# pwr_supply.net
KiCad netlist of a schematic drawn in EAGLE
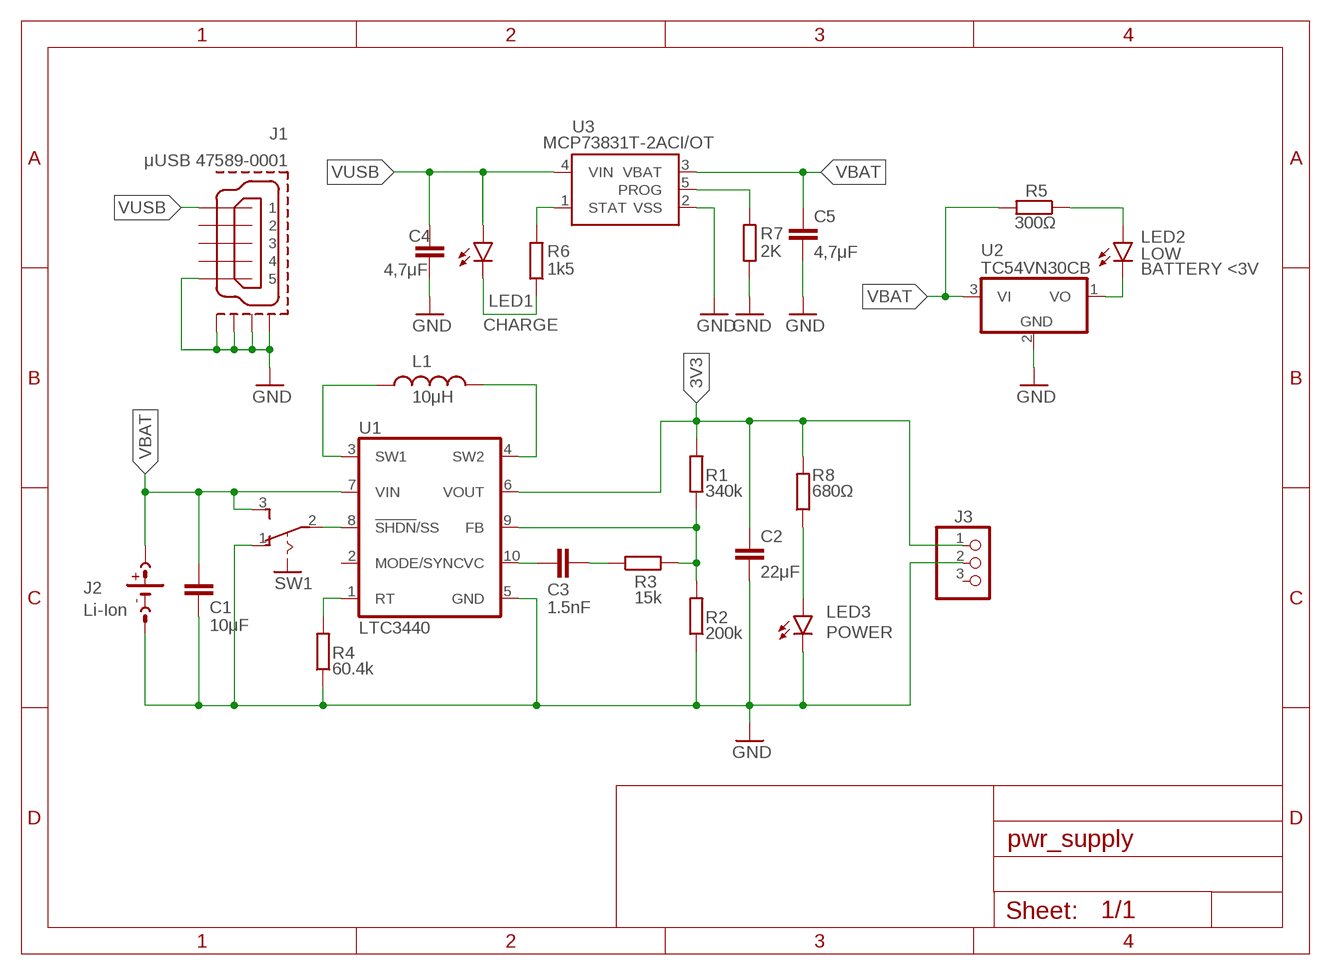
[diagram p0: schematic, sheet 1]

(export (version "E")
  (design (tool "Eeschema 10.0.6"))
  (components
    (comp (ref "C1")
      (value "10μF")
      (footprint "eagle-import:C0805")
      (libsource (lib "eagle-import") (part "C-EUC0805"))
    )
    (comp (ref "C2")
      (value "22μF")
      (footprint "eagle-import:C1210")
      (libsource (lib "eagle-import") (part "C-EUC1210"))
    )
    (comp (ref "C3")
      (value "1.5nF")
      (footprint "eagle-import:C0805")
      (libsource (lib "eagle-import") (part "C-EUC0805"))
    )
    (comp (ref "C4")
      (value "4,7μF")
      (footprint "eagle-import:C0805")
      (libsource (lib "eagle-import") (part "C-EUC0805"))
    )
    (comp (ref "C5")
      (value "4,7μF")
      (footprint "eagle-import:C0805")
      (libsource (lib "eagle-import") (part "C-EUC0805"))
    )
    (comp (ref "J1")
      (value "μUSB 47589-0001")
      (footprint "eagle-import:47589-0001")
      (libsource (lib "eagle-import") (part "MICRO-USB-RECEPTACLE47589-0001"))
    )
    (comp (ref "J2")
      (value "Li-Ion")
      (footprint "eagle-import:JSTPH2")
      (libsource (lib "eagle-import") (part "LION_3V7_JST2"))
    )
    (comp (ref "J3")
      (value "PINHD-1X3/90")
      (footprint "eagle-import:1X03_90")
      (libsource (lib "eagle-import") (part "PINHD-1X3/90"))
    )
    (comp (ref "L1")
      (value "10μH")
      (footprint "eagle-import:CDRH6D38")
      (libsource (lib "eagle-import") (part "CDRH6D38"))
    )
    (comp (ref "LED1")
      (value "CHARGE")
      (footprint "eagle-import:CHIPLED_0805")
      (libsource (lib "eagle-import") (part "LEDCHIPLED_0805"))
    )
    (comp (ref "LED2")
      (value "LOW")
      (footprint "eagle-import:CHIPLED_0805")
      (libsource (lib "eagle-import") (part "LEDCHIPLED_0805"))
    )
    (comp (ref "LED3")
      (value "POWER")
      (footprint "eagle-import:CHIPLED_0805")
      (libsource (lib "eagle-import") (part "LEDCHIPLED_0805"))
    )
    (comp (ref "R1")
      (value "340k")
      (footprint "eagle-import:R0805")
      (libsource (lib "eagle-import") (part "R-EU_R0805"))
    )
    (comp (ref "R2")
      (value "200k")
      (footprint "eagle-import:R0805")
      (libsource (lib "eagle-import") (part "R-EU_R0805"))
    )
    (comp (ref "R3")
      (value "15k")
      (footprint "eagle-import:R0805")
      (libsource (lib "eagle-import") (part "R-EU_R0805"))
    )
    (comp (ref "R4")
      (value "60.4k")
      (footprint "eagle-import:R0805")
      (libsource (lib "eagle-import") (part "R-EU_R0805"))
    )
    (comp (ref "R5")
      (value "300Ω")
      (footprint "eagle-import:R0805")
      (libsource (lib "eagle-import") (part "R-EU_R0805"))
    )
    (comp (ref "R6")
      (value "1k5")
      (footprint "eagle-import:R0805")
      (libsource (lib "eagle-import") (part "R-EU_R0805"))
    )
    (comp (ref "R7")
      (value "2K")
      (footprint "eagle-import:R0805")
      (libsource (lib "eagle-import") (part "R-EU_R0805"))
    )
    (comp (ref "R8")
      (value "680Ω")
      (footprint "eagle-import:R0805")
      (libsource (lib "eagle-import") (part "R-EU_R0805"))
    )
    (comp (ref "SW1")
      (value "JS102011SAQN")
      (footprint "eagle-import:JS102011SAQN")
      (libsource (lib "eagle-import") (part "JS102011SAQN"))
    )
    (comp (ref "U1")
      (value "LTC3440")
      (footprint "eagle-import:MSOP10")
      (libsource (lib "eagle-import") (part "LTC3440"))
    )
    (comp (ref "U2")
      (value "TC54VN30CB")
      (footprint "eagle-import:SOT23")
      (libsource (lib "eagle-import") (part "TC54VN3002ECB713"))
    )
    (comp (ref "U3")
      (value "MCP73831T-2ACI/OT")
      (footprint "eagle-import:SOT23-5")
      (libsource (lib "eagle-import") (part "MCP73831"))
    )
  )
  (nets
    (net (code "1") (name "3V3") (class "Default")
      (node (ref "C2") (pin "1") (pinfunction "1_1") (pintype "passive"))
      (node (ref "J3") (pin "1") (pinfunction "1_1") (pintype "passive"))
      (node (ref "R1") (pin "2") (pinfunction "2_2") (pintype "passive"))
      (node (ref "R8") (pin "2") (pinfunction "2_2") (pintype "passive"))
      (node (ref "U1") (pin "6") (pinfunction "VOUT_6") (pintype "output"))
    )
    (net (code "2") (name "GND") (class "Default")
      (node (ref "C1") (pin "2") (pinfunction "2_2") (pintype "passive"))
      (node (ref "C2") (pin "2") (pinfunction "2_2") (pintype "passive"))
      (node (ref "C4") (pin "2") (pinfunction "2_2") (pintype "passive"))
      (node (ref "C5") (pin "2") (pinfunction "2_2") (pintype "passive"))
      (node (ref "J1") (pin "5") (pinfunction "5_5") (pintype "input"))
      (node (ref "J1") (pin "CASING1") (pinfunction "GND1_CASING1") (pintype "bidirectional"))
      (node (ref "J1") (pin "CASING2") (pinfunction "GND2_CASING2") (pintype "bidirectional"))
      (node (ref "J1") (pin "CASING3") (pinfunction "GND3_CASING3") (pintype "bidirectional"))
      (node (ref "J1") (pin "CASING4") (pinfunction "GND4_CASING4") (pintype "bidirectional"))
      (node (ref "J2") (pin "1") (pinfunction "-_1") (pintype "power_in"))
      (node (ref "J3") (pin "2") (pinfunction "2_2") (pintype "passive"))
      (node (ref "LED3") (pin "C") (pinfunction "C_C") (pintype "passive"))
      (node (ref "R2") (pin "1") (pinfunction "1_1") (pintype "passive"))
      (node (ref "R4") (pin "1") (pinfunction "1_1") (pintype "passive"))
      (node (ref "R7") (pin "1") (pinfunction "1_1") (pintype "passive"))
      (node (ref "SW1") (pin "1") (pinfunction "O_1") (pintype "passive"))
      (node (ref "U1") (pin "5") (pinfunction "GND_5") (pintype "power_in"))
      (node (ref "U2") (pin "2") (pinfunction "GND_2") (pintype "passive"))
      (node (ref "U3") (pin "2") (pinfunction "VSS_2") (pintype "power_in"))
    )
    (net (code "3") (name "Net-(C3-Pad2)") (class "Default")
      (node (ref "C3") (pin "2") (pinfunction "2_2") (pintype "passive"))
      (node (ref "R3") (pin "1") (pinfunction "1_1") (pintype "passive"))
    )
    (net (code "4") (name "Net-(LED1-PadC)") (class "Default")
      (node (ref "LED1") (pin "C") (pinfunction "C_C") (pintype "passive"))
      (node (ref "R6") (pin "1") (pinfunction "1_1") (pintype "passive"))
    )
    (net (code "5") (name "Net-(LED2-PadA)") (class "Default")
      (node (ref "LED2") (pin "A") (pinfunction "A_A") (pintype "passive"))
      (node (ref "R5") (pin "1") (pinfunction "1_1") (pintype "passive"))
    )
    (net (code "6") (name "Net-(LED3-PadA)") (class "Default")
      (node (ref "LED3") (pin "A") (pinfunction "A_A") (pintype "passive"))
      (node (ref "R8") (pin "1") (pinfunction "1_1") (pintype "passive"))
    )
    (net (code "7") (name "Net-(SW1-P)") (class "Default")
      (node (ref "SW1") (pin "2") (pinfunction "P_2") (pintype "passive"))
      (node (ref "U1") (pin "8") (pinfunction "~{SHDN}/SS_8") (pintype "input"))
    )
    (net (code "8") (name "Net-(U1-FB)") (class "Default")
      (node (ref "R1") (pin "1") (pinfunction "1_1") (pintype "passive"))
      (node (ref "R2") (pin "2") (pinfunction "2_2") (pintype "passive"))
      (node (ref "R3") (pin "2") (pinfunction "2_2") (pintype "passive"))
      (node (ref "U1") (pin "9") (pinfunction "FB_9") (pintype "input"))
    )
    (net (code "9") (name "Net-(U1-RT)") (class "Default")
      (node (ref "R4") (pin "2") (pinfunction "2_2") (pintype "passive"))
      (node (ref "U1") (pin "1") (pinfunction "RT_1") (pintype "input"))
    )
    (net (code "10") (name "Net-(U1-SW1)") (class "Default")
      (node (ref "L1") (pin "1") (pinfunction "1_1") (pintype "passive"))
      (node (ref "U1") (pin "3") (pinfunction "SW1_3") (pintype "input"))
    )
    (net (code "11") (name "Net-(U1-SW2)") (class "Default")
      (node (ref "L1") (pin "2") (pinfunction "2_2") (pintype "passive"))
      (node (ref "U1") (pin "4") (pinfunction "SW2_4") (pintype "input"))
    )
    (net (code "12") (name "Net-(U1-VC)") (class "Default")
      (node (ref "C3") (pin "1") (pinfunction "1_1") (pintype "passive"))
      (node (ref "U1") (pin "10") (pinfunction "VC_10") (pintype "input"))
    )
    (net (code "13") (name "Net-(U2-VO)") (class "Default")
      (node (ref "LED2") (pin "C") (pinfunction "C_C") (pintype "passive"))
      (node (ref "U2") (pin "1") (pinfunction "VO_1") (pintype "passive"))
    )
    (net (code "14") (name "Net-(U3-PROG)") (class "Default")
      (node (ref "R7") (pin "2") (pinfunction "2_2") (pintype "passive"))
      (node (ref "U3") (pin "5") (pinfunction "PROG_5") (pintype "input"))
    )
    (net (code "15") (name "Net-(U3-STAT)") (class "Default")
      (node (ref "R6") (pin "2") (pinfunction "2_2") (pintype "passive"))
      (node (ref "U3") (pin "1") (pinfunction "STAT_1") (pintype "output"))
    )
    (net (code "16") (name "VBAT") (class "Default")
      (node (ref "C1") (pin "1") (pinfunction "1_1") (pintype "passive"))
      (node (ref "C5") (pin "1") (pinfunction "1_1") (pintype "passive"))
      (node (ref "J2") (pin "2") (pinfunction "+_2") (pintype "power_in"))
      (node (ref "R5") (pin "2") (pinfunction "2_2") (pintype "passive"))
      (node (ref "SW1") (pin "3") (pinfunction "S_3") (pintype "passive"))
      (node (ref "U1") (pin "7") (pinfunction "VIN_7") (pintype "power_in"))
      (node (ref "U2") (pin "3") (pinfunction "VI_3") (pintype "input"))
      (node (ref "U3") (pin "3") (pinfunction "VBAT_3") (pintype "power_in"))
    )
    (net (code "17") (name "VUSB") (class "Default")
      (node (ref "C4") (pin "1") (pinfunction "1_1") (pintype "passive"))
      (node (ref "J1") (pin "1") (pinfunction "1_1") (pintype "input"))
      (node (ref "LED1") (pin "A") (pinfunction "A_A") (pintype "passive"))
      (node (ref "U3") (pin "4") (pinfunction "VIN_4") (pintype "power_in"))
    )
    (net (code "18") (name "unconnected-(J1-Pad2)") (class "Default")
      (node (ref "J1") (pin "2") (pinfunction "2_2") (pintype "input"))
    )
    (net (code "19") (name "unconnected-(J1-Pad3)") (class "Default")
      (node (ref "J1") (pin "3") (pinfunction "3_3") (pintype "input"))
    )
    (net (code "20") (name "unconnected-(J1-Pad4)") (class "Default")
      (node (ref "J1") (pin "4") (pinfunction "4_4") (pintype "input"))
    )
    (net (code "21") (name "unconnected-(J3-Pad3)") (class "Default")
      (node (ref "J3") (pin "3") (pinfunction "3_3") (pintype "passive"))
    )
    (net (code "22") (name "unconnected-(U1-MODE{slash}SYNC-Pad2)") (class "Default")
      (node (ref "U1") (pin "2") (pinfunction "MODE/SYNC_2") (pintype "input"))
    )
  )
)
